# 230C_5V_PSU_TPS40200.net
KiCad netlist of a schematic drawn in Altium Designer
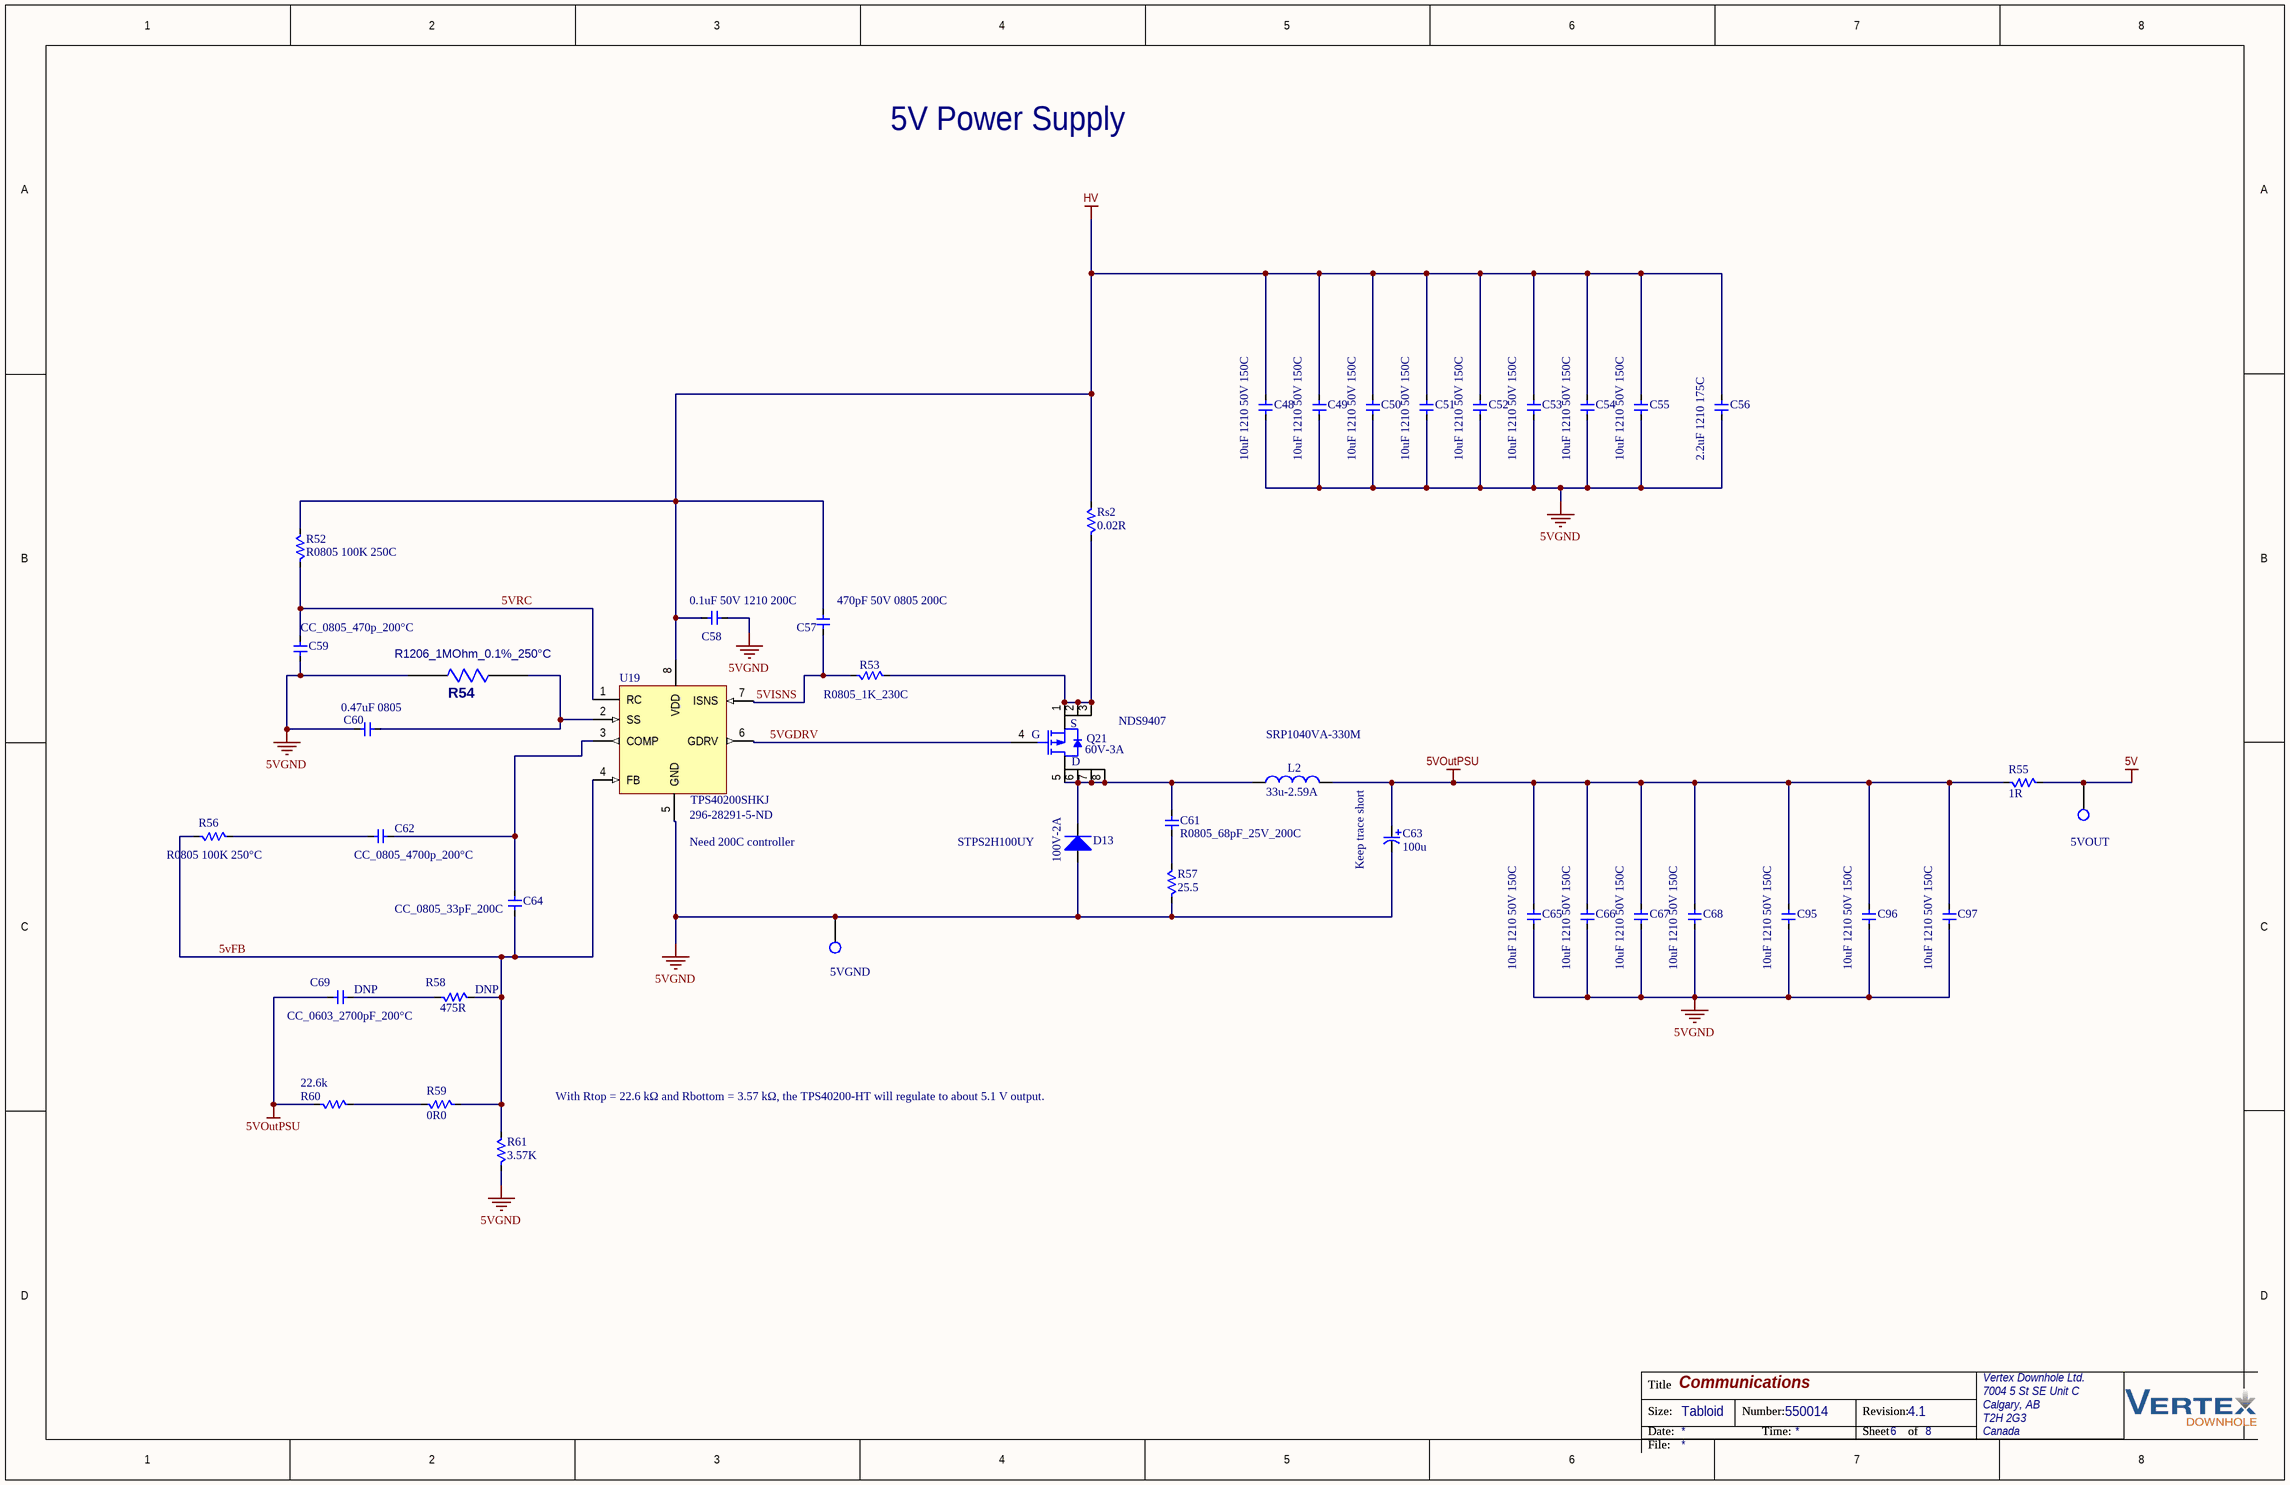
[diagram p0: 230C_5V_PSU_TPS40200.SchDoc]

(export (version "E")
  (design (tool "Eeschema 10.0.6"))
  (components
    (comp (ref "3")
      (value "5VOUT")
      (footprint "TP-S")
      (description "Test  Point")
      (libsource (lib "Miscellaneous") (part "TP"))
    )
    (comp (ref "4")
      (value "5VGND")
      (footprint "TP-S")
      (description "Test  Point")
      (libsource (lib "Miscellaneous") (part "TP"))
    )
    (comp (ref "C48")
      (value "10uF 1210 50V 150C")
      (footprint "1210")
      (description "CAP CER 0.1UF 50V C0G/NP0 1210 200C")
      (fields (field (name "VOLTAGE") "50V") (field (name "TOLERANCE") "±10%"))
      (libsource (lib "230C_PSU_TPS40200") (part "CC-1210"))
    )
    (comp (ref "C49")
      (value "10uF 1210 50V 150C")
      (footprint "1210")
      (description "CAP CER 0.1UF 50V C0G/NP0 1210 200C")
      (fields (field (name "VOLTAGE") "50V") (field (name "TOLERANCE") "±5%"))
      (libsource (lib "230C_PSU_TPS40200") (part "CC-1210"))
    )
    (comp (ref "C50")
      (value "10uF 1210 50V 150C")
      (footprint "1210")
      (description "CAP CER 0.1UF 50V C0G/NP0 1210 200C")
      (fields (field (name "VOLTAGE") "50V") (field (name "TOLERANCE") "±5%"))
      (libsource (lib "230C_PSU_TPS40200") (part "CC-1210"))
    )
    (comp (ref "C51")
      (value "10uF 1210 50V 150C")
      (footprint "1210")
      (description "CAP CER 0.1UF 50V C0G/NP0 1210 200C")
      (fields (field (name "VOLTAGE") "50V") (field (name "TOLERANCE") "±5%"))
      (libsource (lib "230C_PSU_TPS40200") (part "CC-1210"))
    )
    (comp (ref "C52")
      (value "10uF 1210 50V 150C")
      (footprint "1210")
      (description "CAP CER 0.1UF 50V C0G/NP0 1210 200C")
      (fields (field (name "VOLTAGE") "50V") (field (name "TOLERANCE") "±5%"))
      (libsource (lib "230C_PSU_TPS40200") (part "CC-1210"))
    )
    (comp (ref "C53")
      (value "10uF 1210 50V 150C")
      (footprint "1210")
      (description "CAP CER 0.1UF 50V C0G/NP0 1210 200C")
      (fields (field (name "VOLTAGE") "50V") (field (name "TOLERANCE") "±5%"))
      (libsource (lib "230C_PSU_TPS40200") (part "CC-1210"))
    )
    (comp (ref "C54")
      (value "10uF 1210 50V 150C")
      (footprint "1210")
      (description "CAP CER 0.1UF 50V C0G/NP0 1210 200C")
      (fields (field (name "VOLTAGE") "50V") (field (name "TOLERANCE") "±5%"))
      (libsource (lib "230C_PSU_TPS40200") (part "CC-1210"))
    )
    (comp (ref "C55")
      (value "10uF 1210 50V 150C")
      (footprint "1210")
      (description "CAP CER 0.1UF 50V C0G/NP0 1210 200C")
      (fields (field (name "VOLTAGE") "50V") (field (name "TOLERANCE") "±5%"))
      (libsource (lib "230C_PSU_TPS40200") (part "CC-1210"))
    )
    (comp (ref "C56")
      (value "2.2uF 1210 175C")
      (footprint "1210")
      (description "CAP CER 0.1UF 50V C0G/NP0 1210 200C")
      (fields (field (name "VOLTAGE") "25V") (field (name "TOLERANCE") "±5%"))
      (libsource (lib "230C_PSU_TPS40200") (part "CC-1210"))
    )
    (comp (ref "C57")
      (value "470pF 50V 0805 200C")
      (footprint "1210")
      (description "CAP CER 470PF 50V C0G/NP0 0805 200C")
      (fields (field (name "VOLTAGE") "100V") (field (name "TOLERANCE") "±5%"))
      (libsource (lib "Schlib_CES2018") (part "CC-0805-100p-100V-10%-200C-NP0"))
    )
    (comp (ref "C58")
      (value "0.1uF 50V 1210 200C")
      (footprint "0805")
      (description "CAP CER 0.1UF 50V C0G/NP0 1210 200C")
      (fields (field (name "VOLTAGE") "25V") (field (name "TOLERANCE") "±5%"))
      (libsource (lib "230C_PSU_TPS40200") (part "CC-1210"))
    )
    (comp (ref "C59")
      (value "CC_0805_470p_200°C")
      (footprint "0805")
      (description "CAPACITOR CER 470PF 100V C0G/NP0 0805")
      (fields (field (name "VOLTAGE") "100V") (field (name "TOLERANCE") "±10%"))
      (libsource (lib "Integrated_Library_CES2018") (part "CC-0805-470p-100V-10%-150C-NP0"))
    )
    (comp (ref "C60")
      (value "0.47uF 0805")
      (footprint "0805")
      (description "CAPACITOR CER 0.047UF 25V C0G/NP0 0805")
      (fields (field (name "VOLTAGE") "25V") (field (name "TOLERANCE") "±5%"))
      (libsource (lib "Integrated_Library_CES2018") (part "CC-0805-47n-25V-5%-125C-NP0"))
    )
    (comp (ref "C61")
      (value "R0805_68pF_25V_200C")
      (footprint "0805")
      (description "CAPACITOR CER 2200PF 100V C0G/NP0 0805")
      (fields (field (name "VOLTAGE") "100V") (field (name "TOLERANCE") "±5%"))
      (libsource (lib "Schlib_CES2018") (part "CC-0805-2200p-100V-5%-200C-NP0"))
    )
    (comp (ref "C62")
      (value "CC_0805_4700p_200°C")
      (footprint "0805")
      (description "CAPACITOR CER 2200PF 100V C0G/NP0 0805")
      (fields (field (name "VOLTAGE") "100V") (field (name "TOLERANCE") "±5%"))
      (libsource (lib "Schlib_CES2018") (part "CC-0805-2200p-100V-5%-200C-NP0"))
    )
    (comp (ref "C63")
      (value "100u")
      (footprint "0805")
      (description "CAPACITOR TANT 100UF 16V 10% 2917")
      (fields (field (name "VOLTAGE") "16V") (field (name "TOLERANCE") "±10%"))
      (libsource (lib "Integrated_Library_CES2018") (part "CT-2917-100u-16V-10%-150C"))
    )
    (comp (ref "C64")
      (value "CC_0805_33pF_200C")
      (footprint "1210")
      (description "CAPACITOR CER 120PF 250V NP0 0805")
      (fields (field (name "VOLTAGE") "250V") (field (name "TOLERANCE") "±5%"))
      (libsource (lib "Schlib_CES2018") (part "CC-0805-120p-100V-5%-200C-NP0"))
    )
    (comp (ref "C65")
      (value "10uF 1210 50V 150C")
      (footprint "1210")
      (description "CAP CER 0.1UF 50V C0G/NP0 1210 200C")
      (fields (field (name "VOLTAGE") "50V") (field (name "TOLERANCE") "±10%"))
      (libsource (lib "230C_PSU_TPS40200") (part "CC-1210"))
    )
    (comp (ref "C66")
      (value "10uF 1210 50V 150C")
      (footprint "1210")
      (description "CAP CER 0.1UF 50V C0G/NP0 1210 200C")
      (fields (field (name "VOLTAGE") "50V") (field (name "TOLERANCE") "±5%"))
      (libsource (lib "230C_PSU_TPS40200") (part "CC-1210"))
    )
    (comp (ref "C67")
      (value "10uF 1210 50V 150C")
      (footprint "1210")
      (description "CAP CER 0.1UF 50V C0G/NP0 1210 200C")
      (fields (field (name "VOLTAGE") "50V") (field (name "TOLERANCE") "±5%"))
      (libsource (lib "230C_PSU_TPS40200") (part "CC-1210"))
    )
    (comp (ref "C68")
      (value "10uF 1210 50V 150C")
      (footprint "1210")
      (description "CAP CER 0.1UF 50V C0G/NP0 1210 200C")
      (fields (field (name "VOLTAGE") "50V") (field (name "TOLERANCE") "±5%"))
      (libsource (lib "230C_PSU_TPS40200") (part "CC-1210"))
    )
    (comp (ref "C69")
      (value "CC_0603_2700pF_200°C")
      (footprint "0603")
      (description "CAPACITOR CER 2700PF 50V X8R 0805")
      (fields (field (name "VOLTAGE") "50V") (field (name "TOLERANCE") "±5%"))
      (libsource (lib "Integrated_Library_Greg") (part "CC-0805-2700p-50V-10%-150C"))
    )
    (comp (ref "C95")
      (value "10uF 1210 50V 150C")
      (footprint "1210")
      (description "CAP CER 0.1UF 50V C0G/NP0 1210 200C")
      (fields (field (name "VOLTAGE") "50V") (field (name "TOLERANCE") "±5%"))
      (libsource (lib "230C_PSU_TPS40200") (part "CC-1210"))
    )
    (comp (ref "C96")
      (value "10uF 1210 50V 150C")
      (footprint "1210")
      (description "CAP CER 0.1UF 50V C0G/NP0 1210 200C")
      (fields (field (name "VOLTAGE") "50V") (field (name "TOLERANCE") "±5%"))
      (libsource (lib "230C_PSU_TPS40200") (part "CC-1210"))
    )
    (comp (ref "C97")
      (value "10uF 1210 50V 150C")
      (footprint "1210")
      (description "CAP CER 0.1UF 50V C0G/NP0 1210 200C")
      (fields (field (name "VOLTAGE") "50V") (field (name "TOLERANCE") "±5%"))
      (libsource (lib "230C_PSU_TPS40200") (part "CC-1210"))
    )
    (comp (ref "D13")
      (value "100V-2A")
      (footprint "SMB")
      (description "DIODE SCHOTTKY 100V 2A SMB")
      (fields (field (name "VOLTAGE") "100V") (field (name "MFG") "STMicroelectronics"))
      (libsource (lib "Integrated_Library_CES2018") (part "DS-SMB-100V-2A"))
    )
    (comp (ref "L2")
      (value "33u-2.59A")
      (footprint "IND_CB_DRA125")
      (description "INDUCTOR 47UH 2.59A 81 MOHM")
      (fields (field (name "MFG") "Eaton") (field (name "TOLERANCE") "±20%"))
      (libsource (lib "Integrated_Library_CES2018") (part "LL-12.5X12.5-47u-2.59A"))
    )
    (comp (ref "Q21")
      (value "60V-3A")
      (footprint "SOIC_S9407_ONS")
      (description "MOSFET P-CH 60V 3A 8-SOIC")
      (fields (field (name "VOLTAGE") "60V") (field (name "MFG") "ON Semiconductor"))
      (libsource (lib "Integrated_Library_CES2018") (part "QF-SOIC8-PCH-60V-3A"))
    )
    (comp (ref "R52")
      (value "R0805 100K 250C")
      (footprint "0805")
      (description "100 kOhms ±0.1% 0.2W, 1/5W Chip Resistor 0805 (2012 Metric)")
      (fields (field (name "TOLERANCE") "±0.1%") (field (name "MFG") "Vishay Dale Thin Film"))
      (libsource (lib "Schlib_CES2018") (part "RS-0805-9.1K-0.1%-1/4W-155C"))
    )
    (comp (ref "R53")
      (value "R0805_1K_230C")
      (footprint "0805")
      (description "RESISTOR SMD 1K OHM 0.1% 1/8W 0805")
      (fields (field (name "TOLERANCE") "±1%") (field (name "MFG") "Vishay / Sfernice"))
      (libsource (lib "Schlib_CES2018") (part "RS-0805-1K-0.1%-1/8W-155C"))
    )
    (comp (ref "R54")
      (value "R1206_1MOhm_0.1%_250°C")
      (footprint "1206")
      (description "1206")
      (fields (field (name "MPN") "PATT1206E1004BGT1") (field (name "MFR") "Vishay Dale Thin Film"))
      (libsource (lib "BJPPS") (part "RC_1206"))
    )
    (comp (ref "R55")
      (value "1R")
      (footprint "0805")
      (description "RESISTOR SMD 1 OHM 1% 1/4W 0805")
      (fields (field (name "TOLERANCE") "±1%") (field (name "MFG") "Stackpole Electronics Inc."))
      (libsource (lib "Integrated_Library_Greg") (part "RS-0805-1R-1%-0.25W-155C"))
    )
    (comp (ref "R56")
      (value "R0805 100K 250°C")
      (footprint "0805")
      (description "100 kOhms ±0.1% 0.2W, 1/5W Chip Resistor 0805 (2012 Metric)")
      (fields (field (name "TOLERANCE") "±0.1%") (field (name "MFG") "Vishay Dale Thin Film"))
      (libsource (lib "Schlib_CES2018") (part "RS-0805-9.1K-0.1%-1/4W-155C"))
    )
    (comp (ref "R57")
      (value "25.5")
      (footprint "0805")
      (description "RESISTOR SMD 10.2K OHM 1% 1/4W 0805")
      (fields (field (name "TOLERANCE") "±1%") (field (name "MFG") "Panasonic Electronic Components"))
      (libsource (lib "Schlib_CES2018") (part "RS-0805-10.2K-0.1%-0.25W-155C"))
    )
    (comp (ref "R58")
      (value "475R")
      (footprint "0805")
      (description "RESISTOR SMD 475 OHM 0.1% 1/10W 0805")
      (fields (field (name "TOLERANCE") "±0.1%") (field (name "MFG") "Panasonic Electronic Components"))
      (libsource (lib "Schlib_CES2018") (part "RS-0805-475R-0.1%-0.25W-155C"))
    )
    (comp (ref "R59")
      (value "0R0")
      (footprint "0805")
      (fields
        (field (name "TOLERANCE") "±0.1%")
        (field (name "MFG") "Vishay Dale Thin Film")
        (field (name "POWER") "0.250W")
      )
      (libsource (lib "Schlib_CES2018") (part "RS-0805-1.5K-0.1%-1/4W-155C"))
    )
    (comp (ref "R60")
      (value "22.6k")
      (footprint "0805")
      (description "100 kOhms ±0.1% 0.2W, 1/5W Chip Resistor 0805 (2012 Metric)")
      (fields (field (name "TOLERANCE") "±0.1%") (field (name "MFG") "Vishay Dale Thin Film"))
      (libsource (lib "Schlib_CES2018") (part "RS-0805-9.1K-0.1%-1/4W-155C"))
    )
    (comp (ref "R61")
      (value "3.57K")
      (footprint "0805")
      (description "RESISTOR SMD 49.9 OHM 0.1% 1/25W 0805")
      (fields (field (name "TOLERANCE") "±0.1%") (field (name "MFG") "KOA Speer Electronics, Inc."))
      (libsource (lib "Schlib_CES2018") (part "RS-0805-49.9R-0.25%-0.25W-155C"))
    )
    (comp (ref "Rs2")
      (value "0.02R")
      (footprint "1206")
      (description "RESISTOR SMD 0.02 OHM 1% 1W 1206")
      (fields (field (name "TOLERANCE") "±1%") (field (name "MFG") "Panasonic Electronic Components"))
      (libsource (lib "Integrated_Library_CES2018") (part "RS-1206-0.02R-1%-1W-155C"))
    )
    (comp (ref "U19")
      (value "TPS40200SHKJ")
      (footprint "SOIC_S9407_ONS")
      (description "IC REG CTRLR BUCK 8CFP")
      (fields
        (field (name "MFG") "Texas Instruments")
        (field (name "SUPPLIER PART NUMBER 1") "296-28291-5-ND")
      )
      (libsource (lib "Integrated_Library_CES2018") (part "UP-SREG-CFP8-Buck-ADJ-TPS40200"))
    )
  )
  (nets
    (net (code "1") (name "/5VGDRV") (class "Default")
      (node (ref "Q21") (pin "4") (pinfunction "G_4") (pintype "passive"))
      (node (ref "U19") (pin "6") (pinfunction "GDRV_6") (pintype "output"))
    )
    (net (code "2") (name "/5VISNS") (class "Default")
      (node (ref "C57") (pin "2") (pinfunction "2_2") (pintype "passive"))
      (node (ref "R53") (pin "1") (pinfunction "1_1") (pintype "passive"))
      (node (ref "U19") (pin "7") (pinfunction "ISNS_7") (pintype "input"))
    )
    (net (code "3") (name "/5VRC") (class "Default")
      (node (ref "C59") (pin "2") (pinfunction "2_2") (pintype "passive"))
      (node (ref "R52") (pin "1") (pinfunction "1_1") (pintype "passive"))
      (node (ref "U19") (pin "1") (pinfunction "RC_1") (pintype "passive"))
    )
    (net (code "4") (name "/5vFB") (class "Default")
      (node (ref "C64") (pin "1") (pinfunction "1_1") (pintype "passive"))
      (node (ref "R56") (pin "1") (pinfunction "1_1") (pintype "passive"))
      (node (ref "R58") (pin "2") (pinfunction "2_2") (pintype "passive"))
      (node (ref "R59") (pin "1") (pinfunction "1_1") (pintype "passive"))
      (node (ref "R61") (pin "2") (pinfunction "2_2") (pintype "passive"))
      (node (ref "U19") (pin "4") (pinfunction "FB_4") (pintype "input"))
    )
    (net (code "5") (name "5V") (class "Default")
      (node (ref "3") (pin "1") (pinfunction "1_1") (pintype "passive"))
      (node (ref "R55") (pin "2") (pinfunction "2_2") (pintype "passive"))
    )
    (net (code "6") (name "5VGND") (class "Default")
      (node (ref "4") (pin "1") (pinfunction "1_1") (pintype "passive"))
      (node (ref "C48") (pin "1") (pinfunction "1_1") (pintype "passive"))
      (node (ref "C49") (pin "1") (pinfunction "1_1") (pintype "passive"))
      (node (ref "C50") (pin "1") (pinfunction "1_1") (pintype "passive"))
      (node (ref "C51") (pin "1") (pinfunction "1_1") (pintype "passive"))
      (node (ref "C52") (pin "1") (pinfunction "1_1") (pintype "passive"))
      (node (ref "C53") (pin "1") (pinfunction "1_1") (pintype "passive"))
      (node (ref "C54") (pin "1") (pinfunction "1_1") (pintype "passive"))
      (node (ref "C55") (pin "1") (pinfunction "1_1") (pintype "passive"))
      (node (ref "C56") (pin "1") (pinfunction "1_1") (pintype "passive"))
      (node (ref "C58") (pin "2") (pinfunction "2_2") (pintype "passive"))
      (node (ref "C59") (pin "1") (pinfunction "1_1") (pintype "passive"))
      (node (ref "C60") (pin "1") (pinfunction "1_1") (pintype "passive"))
      (node (ref "C63") (pin "2") (pinfunction "2_2") (pintype "passive"))
      (node (ref "C65") (pin "1") (pinfunction "1_1") (pintype "passive"))
      (node (ref "C66") (pin "1") (pinfunction "1_1") (pintype "passive"))
      (node (ref "C67") (pin "1") (pinfunction "1_1") (pintype "passive"))
      (node (ref "C68") (pin "1") (pinfunction "1_1") (pintype "passive"))
      (node (ref "C95") (pin "1") (pinfunction "1_1") (pintype "passive"))
      (node (ref "C96") (pin "1") (pinfunction "1_1") (pintype "passive"))
      (node (ref "C97") (pin "1") (pinfunction "1_1") (pintype "passive"))
      (node (ref "D13") (pin "A") (pinfunction "A_A") (pintype "passive"))
      (node (ref "R54") (pin "1") (pinfunction "A_1") (pintype "passive"))
      (node (ref "R57") (pin "1") (pinfunction "1_1") (pintype "passive"))
      (node (ref "R61") (pin "1") (pinfunction "1_1") (pintype "passive"))
      (node (ref "U19") (pin "5") (pinfunction "GND_5") (pintype "passive"))
    )
    (net (code "7") (name "5VOutPSU") (class "Default")
      (node (ref "C63") (pin "1") (pinfunction "1_1") (pintype "passive"))
      (node (ref "C65") (pin "2") (pinfunction "2_2") (pintype "passive"))
      (node (ref "C66") (pin "2") (pinfunction "2_2") (pintype "passive"))
      (node (ref "C67") (pin "2") (pinfunction "2_2") (pintype "passive"))
      (node (ref "C68") (pin "2") (pinfunction "2_2") (pintype "passive"))
      (node (ref "C69") (pin "1") (pinfunction "1_1") (pintype "passive"))
      (node (ref "C95") (pin "2") (pinfunction "2_2") (pintype "passive"))
      (node (ref "C96") (pin "2") (pinfunction "2_2") (pintype "passive"))
      (node (ref "C97") (pin "2") (pinfunction "2_2") (pintype "passive"))
      (node (ref "L2") (pin "2") (pinfunction "2_2") (pintype "passive"))
      (node (ref "R55") (pin "1") (pinfunction "1_1") (pintype "passive"))
      (node (ref "R60") (pin "1") (pinfunction "1_1") (pintype "passive"))
    )
    (net (code "8") (name "HV") (class "Default")
      (node (ref "C48") (pin "2") (pinfunction "2_2") (pintype "passive"))
      (node (ref "C49") (pin "2") (pinfunction "2_2") (pintype "passive"))
      (node (ref "C50") (pin "2") (pinfunction "2_2") (pintype "passive"))
      (node (ref "C51") (pin "2") (pinfunction "2_2") (pintype "passive"))
      (node (ref "C52") (pin "2") (pinfunction "2_2") (pintype "passive"))
      (node (ref "C53") (pin "2") (pinfunction "2_2") (pintype "passive"))
      (node (ref "C54") (pin "2") (pinfunction "2_2") (pintype "passive"))
      (node (ref "C55") (pin "2") (pinfunction "2_2") (pintype "passive"))
      (node (ref "C56") (pin "2") (pinfunction "2_2") (pintype "passive"))
      (node (ref "C57") (pin "1") (pinfunction "1_1") (pintype "passive"))
      (node (ref "C58") (pin "1") (pinfunction "1_1") (pintype "passive"))
      (node (ref "R52") (pin "2") (pinfunction "2_2") (pintype "passive"))
      (node (ref "Rs2") (pin "2") (pinfunction "2_2") (pintype "passive"))
      (node (ref "U19") (pin "8") (pinfunction "VDD_8") (pintype "power_in"))
    )
    (net (code "9") (name "Net-(C61-Pad1)") (class "Default")
      (node (ref "C61") (pin "1") (pinfunction "1_1") (pintype "passive"))
      (node (ref "R57") (pin "2") (pinfunction "2_2") (pintype "passive"))
    )
    (net (code "10") (name "Net-(C61-Pad2)") (class "Default")
      (node (ref "C61") (pin "2") (pinfunction "2_2") (pintype "passive"))
      (node (ref "D13") (pin "K") (pinfunction "K_K") (pintype "passive"))
      (node (ref "L2") (pin "1") (pinfunction "1_1") (pintype "passive"))
      (node (ref "Q21") (pin "5") (pinfunction "D_5") (pintype "passive"))
      (node (ref "Q21") (pin "6") (pinfunction "D_6") (pintype "passive"))
      (node (ref "Q21") (pin "7") (pinfunction "D_7") (pintype "passive"))
      (node (ref "Q21") (pin "8") (pinfunction "D_8") (pintype "passive"))
    )
    (net (code "11") (name "Net-(C62-Pad1)") (class "Default")
      (node (ref "C62") (pin "1") (pinfunction "1_1") (pintype "passive"))
      (node (ref "R56") (pin "2") (pinfunction "2_2") (pintype "passive"))
    )
    (net (code "12") (name "Net-(C69-Pad2)") (class "Default")
      (node (ref "C69") (pin "2") (pinfunction "2_2") (pintype "passive"))
      (node (ref "R58") (pin "1") (pinfunction "1_1") (pintype "passive"))
    )
    (net (code "13") (name "Net-(Q21-S-Pad1)") (class "Default")
      (node (ref "Q21") (pin "1") (pinfunction "S_1") (pintype "passive"))
      (node (ref "Q21") (pin "2") (pinfunction "S_2") (pintype "passive"))
      (node (ref "Q21") (pin "3") (pinfunction "S_3") (pintype "passive"))
      (node (ref "R53") (pin "2") (pinfunction "2_2") (pintype "passive"))
      (node (ref "Rs2") (pin "1") (pinfunction "1_1") (pintype "passive"))
    )
    (net (code "14") (name "Net-(R54-B)") (class "Default")
      (node (ref "C60") (pin "2") (pinfunction "2_2") (pintype "passive"))
      (node (ref "R54") (pin "2") (pinfunction "B_2") (pintype "passive"))
      (node (ref "U19") (pin "2") (pinfunction "SS_2") (pintype "input"))
    )
    (net (code "15") (name "Net-(R59-Pad2)") (class "Default")
      (node (ref "R59") (pin "2") (pinfunction "2_2") (pintype "passive"))
      (node (ref "R60") (pin "2") (pinfunction "2_2") (pintype "passive"))
    )
    (net (code "16") (name "Net-(U19-COMP)") (class "Default")
      (node (ref "C62") (pin "2") (pinfunction "2_2") (pintype "passive"))
      (node (ref "C64") (pin "2") (pinfunction "2_2") (pintype "passive"))
      (node (ref "U19") (pin "3") (pinfunction "COMP_3") (pintype "output"))
    )
  )
)
